# AUDIO_CODEC.net
KiCad netlist of a schematic drawn in Altium Designer
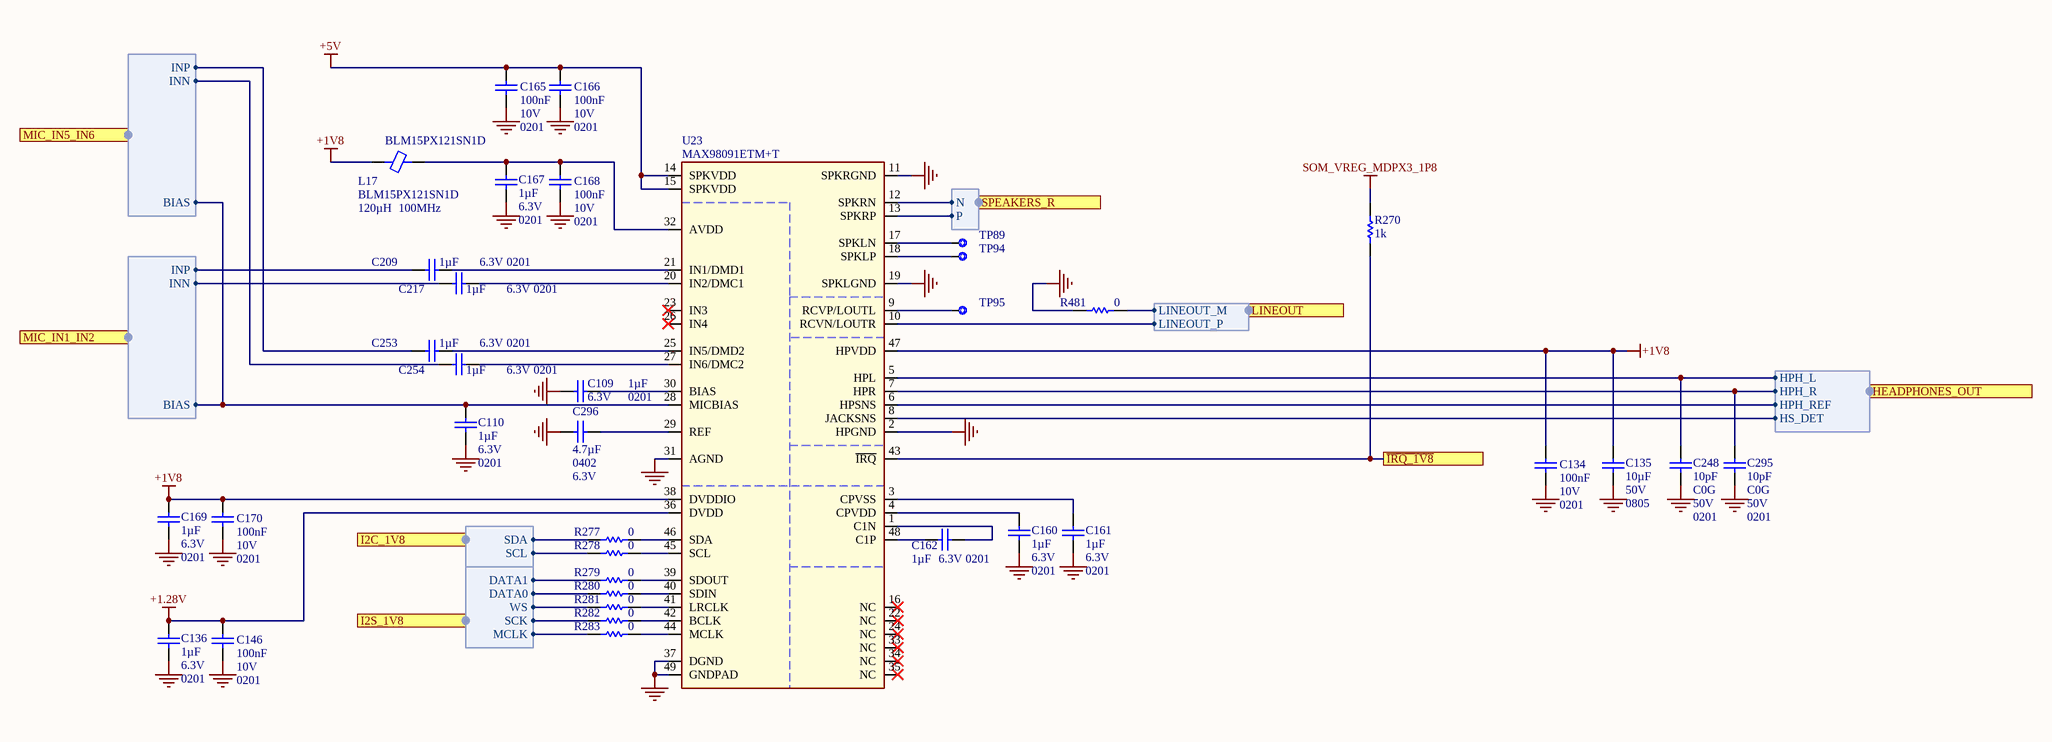
[diagram p0: AUDIO_CODEC.SchDoc]

(export (version "E")
  (design (tool "Eeschema 10.0.6"))
  (components
    (comp (ref "C109")
      (value "1µF")
      (footprint "CAP-0201")
      (description "CAP CHIP 0201 1uF 20% 6.3V X5R")
      (fields
        (field (name "VOLTAGE") "6.3V")
        (field (name "TOLERANCE") "20%")
        (field (name "PART NUMBER") "GRM033R60J105MEA2D")
        (field (name "CASE CODE (IMPERIAL)") "0201")
      )
      (libsource (lib "Clean") (part "CAP"))
    )
    (comp (ref "C110")
      (value "1µF")
      (footprint "CAP-0201")
      (description "CAP CHIP 0201 1uF 20% 6.3V X5R")
      (fields
        (field (name "VOLTAGE") "6.3V")
        (field (name "TOLERANCE") "20%")
        (field (name "PART NUMBER") "GRM033R60J105MEA2D")
        (field (name "CASE CODE (IMPERIAL)") "0201")
      )
      (libsource (lib "Clean") (part "CAP"))
    )
    (comp (ref "C134")
      (value "100nF")
      (footprint "CAP-0201")
      (description "CAP CHIP 0201 100nF 10% 10V X5R")
      (fields
        (field (name "PART NUMBER") "CL03A104KP3NNNC")
        (field (name "MANUFACTURER") "Samsung Electro-Mechanics")
        (field (name "VOLTAGE") "10V")
        (field (name "CASE CODE (IMPERIAL)") "0201")
      )
      (libsource (lib "Clean") (part "CAP"))
    )
    (comp (ref "C135")
      (value "10µF")
      (footprint "CAP-0805")
      (description "CAP CHIP 0805 10uF 20% 50V X5R")
      (fields
        (field (name "MANUFACTURER") "Murata Electronics")
        (field (name "VOLTAGE") "50V")
        (field (name "TOLERANCE") "20%")
        (field (name "CASE CODE (IMPERIAL)") "0805")
      )
      (libsource (lib "Clean") (part "CAP"))
    )
    (comp (ref "C136")
      (value "1µF")
      (footprint "CAP-0201")
      (description "CAP CHIP 0201 1uF 20% 6.3V X5R")
      (fields
        (field (name "VOLTAGE") "6.3V")
        (field (name "TOLERANCE") "20%")
        (field (name "PART NUMBER") "GRM033R60J105MEA2D")
        (field (name "CASE CODE (IMPERIAL)") "0201")
      )
      (libsource (lib "Clean") (part "CAP"))
    )
    (comp (ref "C146")
      (value "100nF")
      (footprint "CAP-0201")
      (description "CAP CHIP 0201 100nF 10% 10V X5R")
      (fields
        (field (name "PART NUMBER") "CL03A104KP3NNNC")
        (field (name "MANUFACTURER") "Samsung Electro-Mechanics")
        (field (name "VOLTAGE") "10V")
        (field (name "CASE CODE (IMPERIAL)") "0201")
      )
      (libsource (lib "Clean") (part "CAP"))
    )
    (comp (ref "C160")
      (value "1µF")
      (footprint "CAP-0201")
      (description "CAP CHIP 0201 1uF 20% 6.3V X5R")
      (fields
        (field (name "VOLTAGE") "6.3V")
        (field (name "TOLERANCE") "20%")
        (field (name "PART NUMBER") "GRM033R60J105MEA2D")
        (field (name "CASE CODE (IMPERIAL)") "0201")
      )
      (libsource (lib "Clean") (part "CAP"))
    )
    (comp (ref "C161")
      (value "1µF")
      (footprint "CAP-0201")
      (description "CAP CHIP 0201 1uF 20% 6.3V X5R")
      (fields
        (field (name "VOLTAGE") "6.3V")
        (field (name "TOLERANCE") "20%")
        (field (name "PART NUMBER") "GRM033R60J105MEA2D")
        (field (name "CASE CODE (IMPERIAL)") "0201")
      )
      (libsource (lib "Clean") (part "CAP"))
    )
    (comp (ref "C162")
      (value "1µF")
      (footprint "CAP-0201")
      (description "CAP CHIP 0201 1uF 20% 6.3V X5R")
      (fields
        (field (name "VOLTAGE") "6.3V")
        (field (name "TOLERANCE") "20%")
        (field (name "PART NUMBER") "GRM033R60J105MEA2D")
        (field (name "CASE CODE (IMPERIAL)") "0201")
      )
      (libsource (lib "Clean") (part "CAP"))
    )
    (comp (ref "C165")
      (value "100nF")
      (footprint "CAP-0201")
      (description "CAP CHIP 0201 100nF 10% 10V X5R")
      (fields
        (field (name "PART NUMBER") "CL03A104KP3NNNC")
        (field (name "MANUFACTURER") "Samsung Electro-Mechanics")
        (field (name "VOLTAGE") "10V")
        (field (name "CASE CODE (IMPERIAL)") "0201")
      )
      (libsource (lib "Clean") (part "CAP"))
    )
    (comp (ref "C166")
      (value "100nF")
      (footprint "CAP-0201")
      (description "CAP CHIP 0201 100nF 10% 10V X5R")
      (fields
        (field (name "PART NUMBER") "CL03A104KP3NNNC")
        (field (name "MANUFACTURER") "Samsung Electro-Mechanics")
        (field (name "VOLTAGE") "10V")
        (field (name "CASE CODE (IMPERIAL)") "0201")
      )
      (libsource (lib "Clean") (part "CAP"))
    )
    (comp (ref "C167")
      (value "1µF")
      (footprint "CAP-0201")
      (description "CAP CHIP 0201 1uF 20% 6.3V X5R")
      (fields
        (field (name "VOLTAGE") "6.3V")
        (field (name "TOLERANCE") "20%")
        (field (name "PART NUMBER") "GRM033R60J105MEA2D")
        (field (name "CASE CODE (IMPERIAL)") "0201")
      )
      (libsource (lib "Clean") (part "CAP"))
    )
    (comp (ref "C168")
      (value "100nF")
      (footprint "CAP-0201")
      (description "CAP CHIP 0201 100nF 10% 10V X5R")
      (fields
        (field (name "PART NUMBER") "CL03A104KP3NNNC")
        (field (name "MANUFACTURER") "Samsung Electro-Mechanics")
        (field (name "VOLTAGE") "10V")
        (field (name "CASE CODE (IMPERIAL)") "0201")
      )
      (libsource (lib "Clean") (part "CAP"))
    )
    (comp (ref "C169")
      (value "1µF")
      (footprint "CAP-0201")
      (description "CAP CHIP 0201 1uF 20% 6.3V X5R")
      (fields
        (field (name "VOLTAGE") "6.3V")
        (field (name "TOLERANCE") "20%")
        (field (name "PART NUMBER") "GRM033R60J105MEA2D")
        (field (name "CASE CODE (IMPERIAL)") "0201")
      )
      (libsource (lib "Clean") (part "CAP"))
    )
    (comp (ref "C170")
      (value "100nF")
      (footprint "CAP-0201")
      (description "CAP CHIP 0201 100nF 10% 10V X5R")
      (fields
        (field (name "PART NUMBER") "CL03A104KP3NNNC")
        (field (name "MANUFACTURER") "Samsung Electro-Mechanics")
        (field (name "VOLTAGE") "10V")
        (field (name "CASE CODE (IMPERIAL)") "0201")
      )
      (libsource (lib "Clean") (part "CAP"))
    )
    (comp (ref "C209")
      (value "1µF")
      (footprint "CAP-0201")
      (description "CAP CHIP 0201 1uF 20% 6.3V X5R")
      (fields
        (field (name "VOLTAGE") "6.3V")
        (field (name "TOLERANCE") "20%")
        (field (name "PART NUMBER") "GRM033R60J105MEA2D")
        (field (name "CASE CODE (IMPERIAL)") "0201")
      )
      (libsource (lib "Clean") (part "CAP"))
    )
    (comp (ref "C217")
      (value "1µF")
      (footprint "CAP-0201")
      (description "CAP CHIP 0201 1uF 20% 6.3V X5R")
      (fields
        (field (name "VOLTAGE") "6.3V")
        (field (name "TOLERANCE") "20%")
        (field (name "PART NUMBER") "GRM033R60J105MEA2D")
        (field (name "CASE CODE (IMPERIAL)") "0201")
      )
      (libsource (lib "Clean") (part "CAP"))
    )
    (comp (ref "C248")
      (value "10pF")
      (footprint "CAP-0201")
      (description "CAP CHIP 0201 10pF 5% 50V C0G")
      (fields
        (field (name "DIELECTRIC") "C0G")
        (field (name "VOLTAGE") "50V")
        (field (name "TOLERANCE") "5%")
        (field (name "PART NUMBER") "CC0201GRNPO9BN100")
        (field (name "CASE CODE (IMPERIAL)") "0201")
      )
      (libsource (lib "Clean") (part "CAP"))
    )
    (comp (ref "C253")
      (value "1µF")
      (footprint "CAP-0201")
      (description "CAP CHIP 0201 1uF 20% 6.3V X5R")
      (fields
        (field (name "VOLTAGE") "6.3V")
        (field (name "TOLERANCE") "20%")
        (field (name "PART NUMBER") "GRM033R60J105MEA2D")
        (field (name "CASE CODE (IMPERIAL)") "0201")
      )
      (libsource (lib "Clean") (part "CAP"))
    )
    (comp (ref "C254")
      (value "1µF")
      (footprint "CAP-0201")
      (description "CAP CHIP 0201 1uF 20% 6.3V X5R")
      (fields
        (field (name "VOLTAGE") "6.3V")
        (field (name "TOLERANCE") "20%")
        (field (name "PART NUMBER") "GRM033R60J105MEA2D")
        (field (name "CASE CODE (IMPERIAL)") "0201")
      )
      (libsource (lib "Clean") (part "CAP"))
    )
    (comp (ref "C295")
      (value "10pF")
      (footprint "CAP-0201")
      (description "CAP CHIP 0201 10pF 5% 50V C0G")
      (fields
        (field (name "DIELECTRIC") "C0G")
        (field (name "VOLTAGE") "50V")
        (field (name "TOLERANCE") "5%")
        (field (name "PART NUMBER") "CC0201GRNPO9BN100")
        (field (name "CASE CODE (IMPERIAL)") "0201")
      )
      (libsource (lib "Clean") (part "CAP"))
    )
    (comp (ref "C296")
      (value "4.7µF")
      (footprint "CAP-0402")
      (description "CAP CHIP 0402 4.7uF 20% 6V3 X5R")
      (fields
        (field (name "MANUFACTURER") "Hottech")
        (field (name "PART NUMBER") "C1005A475M6R3NT")
        (field (name "CASE CODE (IMPERIAL)") "0402")
        (field (name "VOLTAGE") "6.3V")
      )
      (libsource (lib "Clean") (part "CAP"))
    )
    (comp (ref "L17")
      (value "BLM15PX121SN1D")
      (footprint "L-0402")
      (description "FERRITE SMD 0402 120Ohm 25% 100MHz Ferrite 2A")
      (fields
        (field (name "INDUCTANCE") "120µH")
        (field (name "TEST FREQUENCY") "100MHz")
        (field (name "MANUFACTURER") "Murata")
        (field (name "TOLERANCE") "25%")
        (field (name "PART NUMBER") "BLM15PX121SN1D")
      )
      (libsource (lib "Clean") (part "Ferrite"))
    )
    (comp (ref "R270")
      (value "1k")
      (footprint "RES-0201")
      (description "RES CHIP 0201 1k 1% 1/20W")
      (fields (field (name "POWER") "50mW") (field (name "TOLERANCE") "1%"))
      (libsource (lib "Clean") (part "RES"))
    )
    (comp (ref "R277")
      (value "0")
      (footprint "RES-0201")
      (description "RES CHIP 0201 0R")
      (fields (field (name "MANUFACTURER") "Vishay") (field (name "PART NUMBER") "CRCW02010000Z0ED"))
      (libsource (lib "Clean") (part "RES"))
    )
    (comp (ref "R278")
      (value "0")
      (footprint "RES-0201")
      (description "RES CHIP 0201 0R")
      (fields (field (name "MANUFACTURER") "Vishay") (field (name "PART NUMBER") "CRCW02010000Z0ED"))
      (libsource (lib "Clean") (part "RES"))
    )
    (comp (ref "R279")
      (value "0")
      (footprint "RES-0201")
      (description "RES CHIP 0201 0R")
      (fields (field (name "MANUFACTURER") "Vishay") (field (name "PART NUMBER") "CRCW02010000Z0ED"))
      (libsource (lib "Clean") (part "RES"))
    )
    (comp (ref "R280")
      (value "0")
      (footprint "RES-0201")
      (description "RES CHIP 0201 0R")
      (fields (field (name "MANUFACTURER") "Vishay") (field (name "PART NUMBER") "CRCW02010000Z0ED"))
      (libsource (lib "Clean") (part "RES"))
    )
    (comp (ref "R281")
      (value "0")
      (footprint "RES-0201")
      (description "RES CHIP 0201 0R")
      (fields (field (name "MANUFACTURER") "Vishay") (field (name "PART NUMBER") "CRCW02010000Z0ED"))
      (libsource (lib "Clean") (part "RES"))
    )
    (comp (ref "R282")
      (value "0")
      (footprint "RES-0201")
      (description "RES CHIP 0201 0R")
      (fields (field (name "MANUFACTURER") "Vishay") (field (name "PART NUMBER") "CRCW02010000Z0ED"))
      (libsource (lib "Clean") (part "RES"))
    )
    (comp (ref "R283")
      (value "0")
      (footprint "RES-0201")
      (description "RES CHIP 0201 0R")
      (fields (field (name "MANUFACTURER") "Vishay") (field (name "PART NUMBER") "CRCW02010000Z0ED"))
      (libsource (lib "Clean") (part "RES"))
    )
    (comp (ref "R481")
      (value "0")
      (footprint "RES-0201")
      (description "RES CHIP 0201 0R")
      (fields (field (name "MANUFACTURER") "Vishay") (field (name "PART NUMBER") "CRCW02010000Z0ED"))
      (libsource (lib "Clean") (part "RES"))
    )
    (comp (ref "TP89")
      (value "Test point 1.00mm")
      (footprint "TP-1.00MM")
      (fields (field (name "PART NUMBER") "This is not a component"))
      (libsource (lib "Clean") (part "TESTPOINT"))
    )
    (comp (ref "TP94")
      (value "Test point 1.00mm")
      (footprint "TP-1.00MM")
      (fields (field (name "PART NUMBER") "This is not a component"))
      (libsource (lib "Clean") (part "TESTPOINT"))
    )
    (comp (ref "TP95")
      (value "Test point 1.00mm")
      (footprint "TP-1.00MM")
      (fields (field (name "PART NUMBER") "This is not a component"))
      (libsource (lib "Clean") (part "TESTPOINT"))
    )
    (comp (ref "U23")
      (value "MAX98091ETM+T")
      (footprint "QFN127P600-8N")
      (fields (field (name "MANUFACTURER") "Analog Devices"))
      (libsource (lib "Clean") (part "MAX98091ETM+T"))
    )
  )
  (nets
    (net (code "7") (name "+1.28V") (class "Default")
      (node (ref "C136") (pin "2") (pinfunction "2_2") (pintype "passive"))
      (node (ref "C146") (pin "2") (pinfunction "2_2") (pintype "passive"))
      (node (ref "U23") (pin "36") (pinfunction "DVDD_36") (pintype "passive"))
    )
    (net (code "8") (name "+1V8") (class "Default")
      (node (ref "C134") (pin "2") (pinfunction "2_2") (pintype "passive"))
      (node (ref "C135") (pin "1") (pinfunction "1_1") (pintype "passive"))
      (node (ref "C169") (pin "2") (pinfunction "2_2") (pintype "passive"))
      (node (ref "C170") (pin "2") (pinfunction "2_2") (pintype "passive"))
      (node (ref "L17") (pin "1") (pinfunction "1_1") (pintype "passive"))
      (node (ref "U23") (pin "38") (pinfunction "DVDDIO_38") (pintype "passive"))
      (node (ref "U23") (pin "47") (pinfunction "HPVDD_47") (pintype "passive"))
    )
    (net (code "9") (name "+5V") (class "Default")
      (node (ref "C165") (pin "2") (pinfunction "2_2") (pintype "passive"))
      (node (ref "C166") (pin "2") (pinfunction "2_2") (pintype "passive"))
      (node (ref "U23") (pin "14") (pinfunction "SPKVDD_14") (pintype "passive"))
      (node (ref "U23") (pin "15") (pinfunction "SPKVDD_15") (pintype "passive"))
    )
    (net (code "16") (name "/~{IRQ_1V8}") (class "Default")
      (node (ref "R270") (pin "1") (pinfunction "1_1") (pintype "passive"))
      (node (ref "U23") (pin "43") (pinfunction "~{IRQ}_43") (pintype "passive"))
    )
    (net (code "17") (name "GND") (class "Default")
      (node (ref "C109") (pin "1") (pinfunction "1_1") (pintype "passive"))
      (node (ref "C110") (pin "1") (pinfunction "1_1") (pintype "passive"))
      (node (ref "C134") (pin "1") (pinfunction "1_1") (pintype "passive"))
      (node (ref "C135") (pin "2") (pinfunction "2_2") (pintype "passive"))
      (node (ref "C136") (pin "1") (pinfunction "1_1") (pintype "passive"))
      (node (ref "C146") (pin "1") (pinfunction "1_1") (pintype "passive"))
      (node (ref "C160") (pin "1") (pinfunction "1_1") (pintype "passive"))
      (node (ref "C161") (pin "1") (pinfunction "1_1") (pintype "passive"))
      (node (ref "C165") (pin "1") (pinfunction "1_1") (pintype "passive"))
      (node (ref "C166") (pin "1") (pinfunction "1_1") (pintype "passive"))
      (node (ref "C167") (pin "1") (pinfunction "1_1") (pintype "passive"))
      (node (ref "C168") (pin "1") (pinfunction "1_1") (pintype "passive"))
      (node (ref "C169") (pin "1") (pinfunction "1_1") (pintype "passive"))
      (node (ref "C170") (pin "1") (pinfunction "1_1") (pintype "passive"))
      (node (ref "C248") (pin "1") (pinfunction "1_1") (pintype "passive"))
      (node (ref "C295") (pin "1") (pinfunction "1_1") (pintype "passive"))
      (node (ref "C296") (pin "2") (pinfunction "2_2") (pintype "passive"))
      (node (ref "R481") (pin "1") (pinfunction "1_1") (pintype "passive"))
      (node (ref "U23") (pin "11") (pinfunction "SPKRGND_11") (pintype "passive"))
      (node (ref "U23") (pin "19") (pinfunction "SPKLGND_19") (pintype "passive"))
      (node (ref "U23") (pin "2") (pinfunction "HPGND_2") (pintype "passive"))
      (node (ref "U23") (pin "31") (pinfunction "AGND_31") (pintype "passive"))
      (node (ref "U23") (pin "37") (pinfunction "DGND_37") (pintype "passive"))
      (node (ref "U23") (pin "49") (pinfunction "GNDPAD_49") (pintype "passive"))
    )
    (net (code "18") (name "Net-(U23-AVDD)") (class "Default")
      (node (ref "C167") (pin "2") (pinfunction "2_2") (pintype "passive"))
      (node (ref "C168") (pin "2") (pinfunction "2_2") (pintype "passive"))
      (node (ref "L17") (pin "2") (pinfunction "2_2") (pintype "passive"))
      (node (ref "U23") (pin "32") (pinfunction "AVDD_32") (pintype "passive"))
    )
    (net (code "19") (name "Net-(U23-BCLK)") (class "Default")
      (node (ref "R282") (pin "2") (pinfunction "2_2") (pintype "passive"))
      (node (ref "U23") (pin "42") (pinfunction "BCLK_42") (pintype "passive"))
    )
    (net (code "20") (name "Net-(U23-BIAS)") (class "Default")
      (node (ref "C109") (pin "2") (pinfunction "2_2") (pintype "passive"))
      (node (ref "U23") (pin "30") (pinfunction "BIAS_30") (pintype "passive"))
    )
    (net (code "21") (name "Net-(U23-C1N)") (class "Default")
      (node (ref "C162") (pin "1") (pinfunction "1_1") (pintype "passive"))
      (node (ref "U23") (pin "1") (pinfunction "C1N_1") (pintype "passive"))
    )
    (net (code "22") (name "Net-(U23-C1P)") (class "Default")
      (node (ref "C162") (pin "2") (pinfunction "2_2") (pintype "passive"))
      (node (ref "U23") (pin "48") (pinfunction "C1P_48") (pintype "passive"))
    )
    (net (code "23") (name "Net-(U23-CPVDD)") (class "Default")
      (node (ref "C160") (pin "2") (pinfunction "2_2") (pintype "passive"))
      (node (ref "U23") (pin "4") (pinfunction "CPVDD_4") (pintype "passive"))
    )
    (net (code "24") (name "Net-(U23-CPVSS)") (class "Default")
      (node (ref "C161") (pin "2") (pinfunction "2_2") (pintype "passive"))
      (node (ref "U23") (pin "3") (pinfunction "CPVSS_3") (pintype "passive"))
    )
    (net (code "25") (name "Net-(U23-HPL)") (class "Default")
      (node (ref "C248") (pin "2") (pinfunction "2_2") (pintype "passive"))
      (node (ref "U23") (pin "5") (pinfunction "HPL_5") (pintype "passive"))
    )
    (net (code "26") (name "Net-(U23-HPR)") (class "Default")
      (node (ref "C295") (pin "2") (pinfunction "2_2") (pintype "passive"))
      (node (ref "U23") (pin "7") (pinfunction "HPR_7") (pintype "passive"))
    )
    (net (code "27") (name "Net-(U23-IN1{slash}DMD1)") (class "Default")
      (node (ref "C209") (pin "1") (pinfunction "1_1") (pintype "passive"))
      (node (ref "U23") (pin "21") (pinfunction "IN1/DMD1_21") (pintype "passive"))
    )
    (net (code "28") (name "Net-(U23-IN2{slash}DMC1)") (class "Default")
      (node (ref "C217") (pin "1") (pinfunction "1_1") (pintype "passive"))
      (node (ref "U23") (pin "20") (pinfunction "IN2/DMC1_20") (pintype "passive"))
    )
    (net (code "29") (name "Net-(U23-IN5{slash}DMD2)") (class "Default")
      (node (ref "C253") (pin "1") (pinfunction "1_1") (pintype "passive"))
      (node (ref "U23") (pin "25") (pinfunction "IN5/DMD2_25") (pintype "passive"))
    )
    (net (code "30") (name "Net-(U23-IN6{slash}DMC2)") (class "Default")
      (node (ref "C254") (pin "1") (pinfunction "1_1") (pintype "passive"))
      (node (ref "U23") (pin "27") (pinfunction "IN6/DMC2_27") (pintype "passive"))
    )
    (net (code "31") (name "Net-(U23-LRCLK)") (class "Default")
      (node (ref "R281") (pin "2") (pinfunction "2_2") (pintype "passive"))
      (node (ref "U23") (pin "41") (pinfunction "LRCLK_41") (pintype "passive"))
    )
    (net (code "32") (name "Net-(U23-MCLK)") (class "Default")
      (node (ref "R283") (pin "2") (pinfunction "2_2") (pintype "passive"))
      (node (ref "U23") (pin "44") (pinfunction "MCLK_44") (pintype "passive"))
    )
    (net (code "33") (name "Net-(U23-MICBIAS)") (class "Default")
      (node (ref "C110") (pin "2") (pinfunction "2_2") (pintype "passive"))
      (node (ref "U23") (pin "28") (pinfunction "MICBIAS_28") (pintype "passive"))
    )
    (net (code "34") (name "Net-(U23-RCVP{slash}LOUTL)") (class "Default")
      (node (ref "TP95") (pin "X") (pinfunction "X_X") (pintype "passive"))
      (node (ref "U23") (pin "9") (pinfunction "RCVP/LOUTL_9") (pintype "passive"))
    )
    (net (code "35") (name "Net-(U23-REF)") (class "Default")
      (node (ref "C296") (pin "1") (pinfunction "1_1") (pintype "passive"))
      (node (ref "U23") (pin "29") (pinfunction "REF_29") (pintype "passive"))
    )
    (net (code "36") (name "Net-(U23-SCL)") (class "Default")
      (node (ref "R278") (pin "2") (pinfunction "2_2") (pintype "passive"))
      (node (ref "U23") (pin "45") (pinfunction "SCL_45") (pintype "passive"))
    )
    (net (code "37") (name "Net-(U23-SDA)") (class "Default")
      (node (ref "R277") (pin "2") (pinfunction "2_2") (pintype "passive"))
      (node (ref "U23") (pin "46") (pinfunction "SDA_46") (pintype "passive"))
    )
    (net (code "38") (name "Net-(U23-SDIN)") (class "Default")
      (node (ref "R280") (pin "2") (pinfunction "2_2") (pintype "passive"))
      (node (ref "U23") (pin "40") (pinfunction "SDIN_40") (pintype "passive"))
    )
    (net (code "39") (name "Net-(U23-SDOUT)") (class "Default")
      (node (ref "R279") (pin "2") (pinfunction "2_2") (pintype "passive"))
      (node (ref "U23") (pin "39") (pinfunction "SDOUT_39") (pintype "passive"))
    )
    (net (code "40") (name "Net-(U23-SPKLN)") (class "Default")
      (node (ref "TP89") (pin "X") (pinfunction "X_X") (pintype "passive"))
      (node (ref "U23") (pin "17") (pinfunction "SPKLN_17") (pintype "passive"))
    )
    (net (code "41") (name "Net-(U23-SPKLP)") (class "Default")
      (node (ref "TP94") (pin "X") (pinfunction "X_X") (pintype "passive"))
      (node (ref "U23") (pin "18") (pinfunction "SPKLP_18") (pintype "passive"))
    )
    (net (code "42") (name "SOM_VREG_MDPX3_1P8") (class "Default")
      (node (ref "R270") (pin "2") (pinfunction "2_2") (pintype "passive"))
    )
    (net (code "43") (name "unconnected-(C209-Pad2)") (class "Default")
      (node (ref "C209") (pin "2") (pinfunction "2_2") (pintype "passive"))
    )
    (net (code "44") (name "unconnected-(C217-Pad2)") (class "Default")
      (node (ref "C217") (pin "2") (pinfunction "2_2") (pintype "passive"))
    )
    (net (code "45") (name "unconnected-(C253-Pad2)") (class "Default")
      (node (ref "C253") (pin "2") (pinfunction "2_2") (pintype "passive"))
    )
    (net (code "46") (name "unconnected-(C254-Pad2)") (class "Default")
      (node (ref "C254") (pin "2") (pinfunction "2_2") (pintype "passive"))
    )
    (net (code "47") (name "unconnected-(R277-Pad1)") (class "Default")
      (node (ref "R277") (pin "1") (pinfunction "1_1") (pintype "passive"))
    )
    (net (code "48") (name "unconnected-(R278-Pad1)") (class "Default")
      (node (ref "R278") (pin "1") (pinfunction "1_1") (pintype "passive"))
    )
    (net (code "49") (name "unconnected-(R279-Pad1)") (class "Default")
      (node (ref "R279") (pin "1") (pinfunction "1_1") (pintype "passive"))
    )
    (net (code "50") (name "unconnected-(R280-Pad1)") (class "Default")
      (node (ref "R280") (pin "1") (pinfunction "1_1") (pintype "passive"))
    )
    (net (code "51") (name "unconnected-(R281-Pad1)") (class "Default")
      (node (ref "R281") (pin "1") (pinfunction "1_1") (pintype "passive"))
    )
    (net (code "52") (name "unconnected-(R282-Pad1)") (class "Default")
      (node (ref "R282") (pin "1") (pinfunction "1_1") (pintype "passive"))
    )
    (net (code "53") (name "unconnected-(R283-Pad1)") (class "Default")
      (node (ref "R283") (pin "1") (pinfunction "1_1") (pintype "passive"))
    )
    (net (code "54") (name "unconnected-(R481-Pad2)") (class "Default")
      (node (ref "R481") (pin "2") (pinfunction "2_2") (pintype "passive"))
    )
    (net (code "55") (name "unconnected-(U23-HPSNS-Pad6)") (class "Default")
      (node (ref "U23") (pin "6") (pinfunction "HPSNS_6") (pintype "passive"))
    )
    (net (code "56") (name "unconnected-(U23-IN3-Pad23)") (class "Default")
      (node (ref "U23") (pin "23") (pinfunction "IN3_23") (pintype "passive+no_connect"))
    )
    (net (code "57") (name "unconnected-(U23-IN4-Pad26)") (class "Default")
      (node (ref "U23") (pin "26") (pinfunction "IN4_26") (pintype "passive+no_connect"))
    )
    (net (code "58") (name "unconnected-(U23-JACKSNS-Pad8)") (class "Default")
      (node (ref "U23") (pin "8") (pinfunction "JACKSNS_8") (pintype "passive"))
    )
    (net (code "59") (name "unconnected-(U23-NC-Pad16)") (class "Default")
      (node (ref "U23") (pin "16") (pinfunction "NC_16") (pintype "passive+no_connect"))
    )
    (net (code "60") (name "unconnected-(U23-NC-Pad22)") (class "Default")
      (node (ref "U23") (pin "22") (pinfunction "NC_22") (pintype "passive+no_connect"))
    )
    (net (code "61") (name "unconnected-(U23-NC-Pad24)") (class "Default")
      (node (ref "U23") (pin "24") (pinfunction "NC_24") (pintype "passive+no_connect"))
    )
    (net (code "62") (name "unconnected-(U23-NC-Pad33)") (class "Default")
      (node (ref "U23") (pin "33") (pinfunction "NC_33") (pintype "passive+no_connect"))
    )
    (net (code "63") (name "unconnected-(U23-NC-Pad34)") (class "Default")
      (node (ref "U23") (pin "34") (pinfunction "NC_34") (pintype "passive+no_connect"))
    )
    (net (code "64") (name "unconnected-(U23-NC-Pad35)") (class "Default")
      (node (ref "U23") (pin "35") (pinfunction "NC_35") (pintype "passive+no_connect"))
    )
    (net (code "65") (name "unconnected-(U23-RCVN{slash}LOUTR-Pad10)") (class "Default")
      (node (ref "U23") (pin "10") (pinfunction "RCVN/LOUTR_10") (pintype "passive"))
    )
    (net (code "66") (name "unconnected-(U23-SPKRN-Pad12)") (class "Default")
      (node (ref "U23") (pin "12") (pinfunction "SPKRN_12") (pintype "passive"))
    )
    (net (code "67") (name "unconnected-(U23-SPKRP-Pad13)") (class "Default")
      (node (ref "U23") (pin "13") (pinfunction "SPKRP_13") (pintype "passive"))
    )
  )
)
